# SH2_-_48V_POWER.net
KiCad netlist of a schematic drawn in Altium Designer
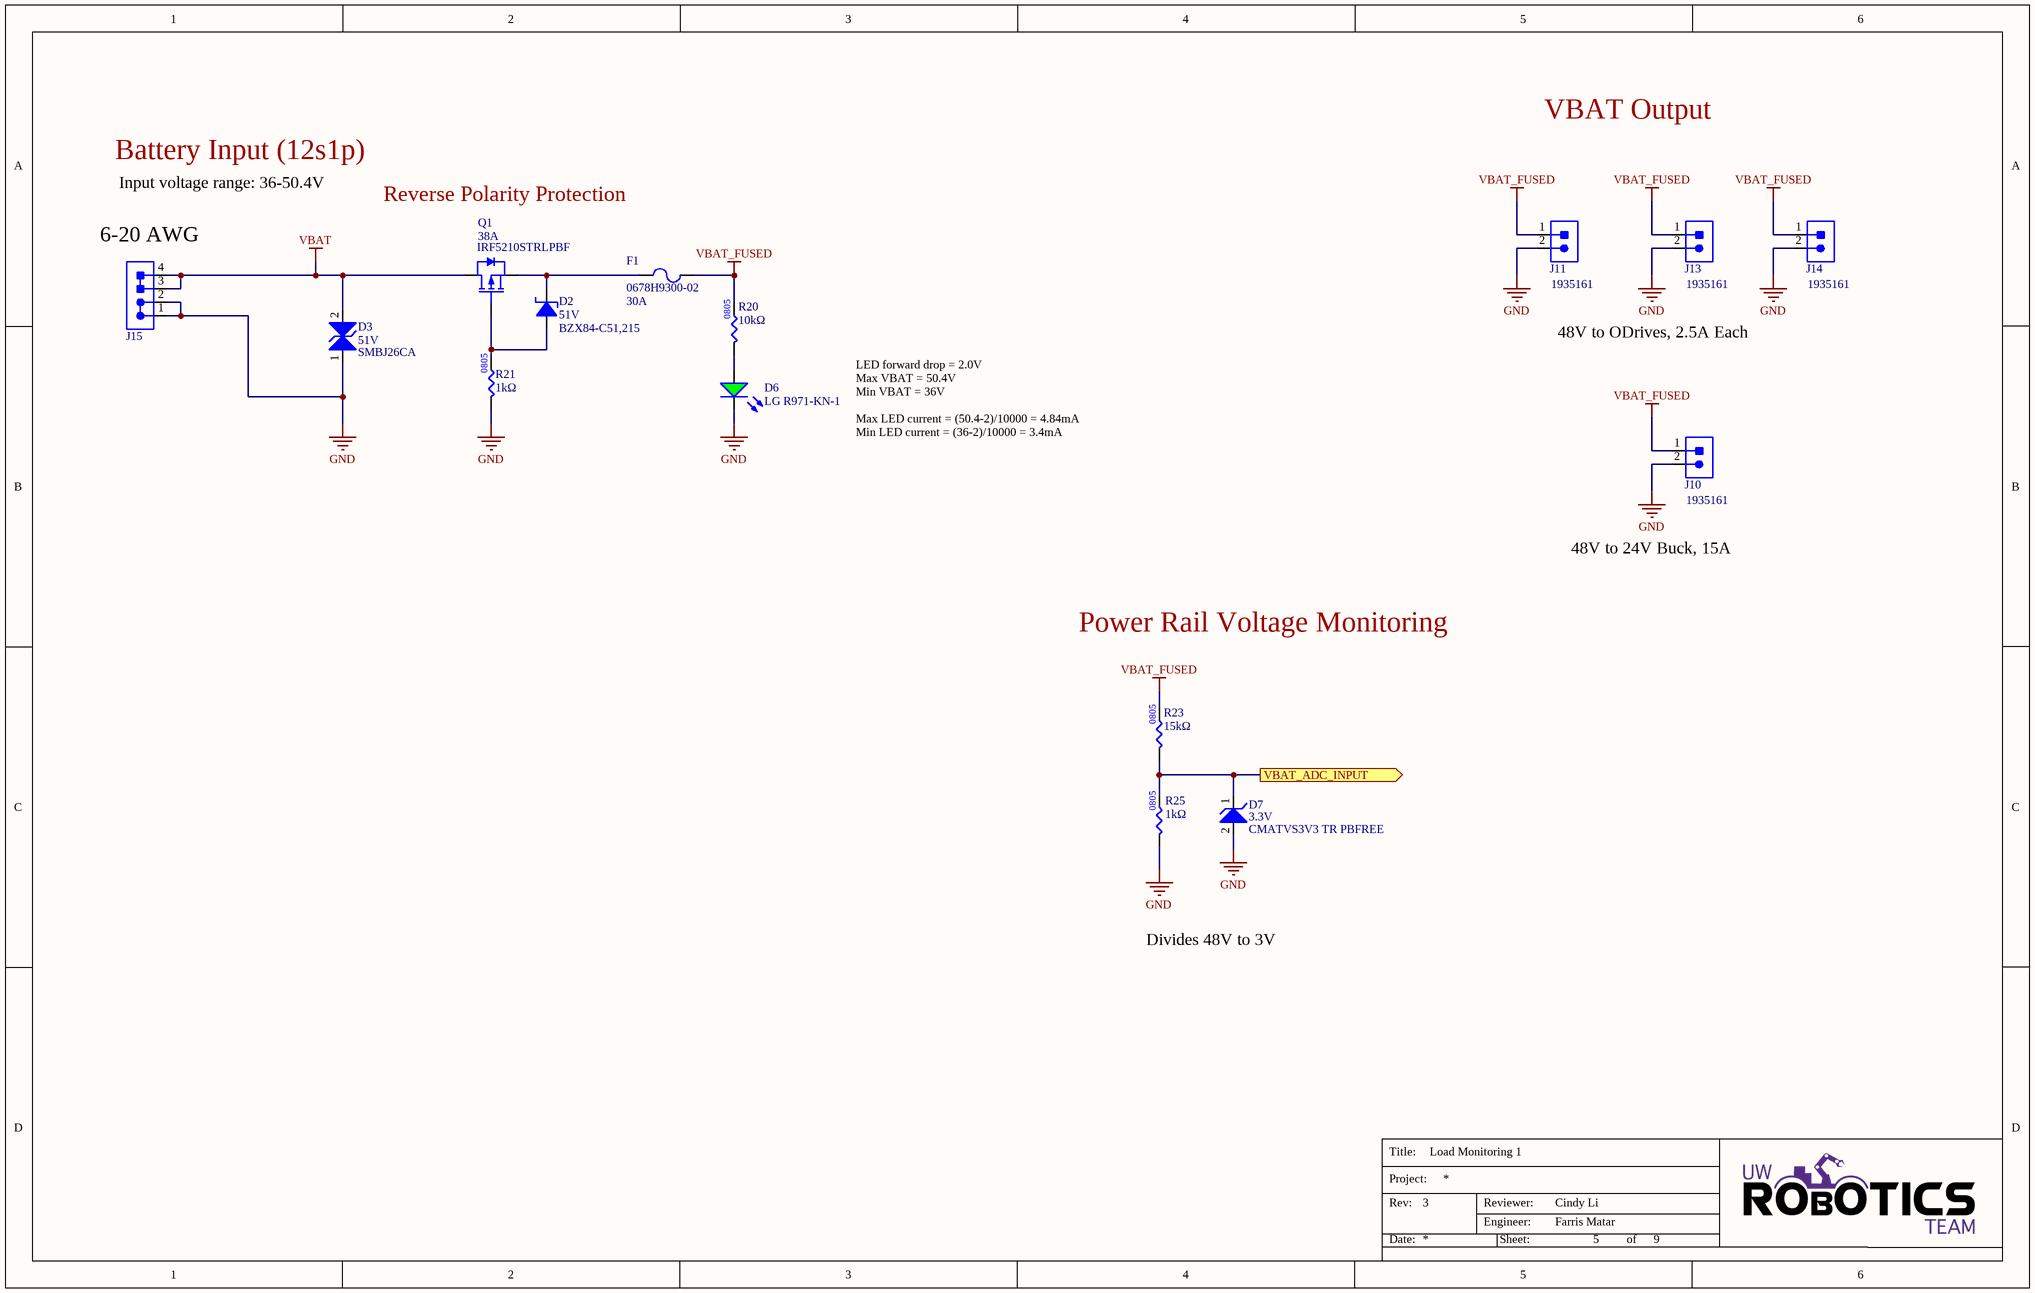
[diagram p0: SH2 - 48V POWER.SchDoc]

(export (version "E")
  (design (tool "Eeschema 10.0.6"))
  (components
    (comp (ref "D2")
      (value "DIO_ZENER_51V")
      (footprint "SOT23-3")
      (description "DIODE ZENER 51V 250MW TO236AB")
      (fields
        (field (name "MANUFACTURER PART NUMBER 1") "BZX84-C51,215")
        (field (name "WORKING VOLTAGE") "51V")
      )
      (libsource (lib "UWRT_Schematic_Library_2020") (part "DIO_ZENER_51V"))
    )
    (comp (ref "D3")
      (value "TVS_DIODE_BIDIR_51V")
      (footprint "TVS_DIODE_BIDIR_SMB")
      (description "TVS DIODE 51VWM 82.4VC DO214AA")
      (fields
        (field (name "MANUFACTURER PART NUMBER 1") "SMBJ26CA")
        (field (name "VOLTAGE - REVERSE STANDOFF (TYP)") "51V")
      )
      (libsource (lib "UWRT_Schematic_Library_2020") (part "TVS_DIODE_BIDIR_51V"))
    )
    (comp (ref "D6")
      (value "LED_GREEN")
      (footprint "LED_0805_GREEN")
      (description "LED GREEN DIFFUSED 0805 SMD")
      (fields (field (name "MANUFACTURER PART NUMBER 1") "LG R971-KN-1"))
      (libsource (lib "UWRT_Schematic_Library_2020") (part "LED_GREEN"))
    )
    (comp (ref "D7")
      (value "TVS_DIODE_UNIDIR_3.3V_7A")
      (footprint "SOD-923")
      (description "TVS DIODE 3.3VWM 11VC SOD923")
      (fields
        (field (name "MANUFACTURER PART NUMBER 1") "CMATVS3V3 TR PBFREE")
        (field (name "VOLTAGE - REVERSE STANDOFF (TYP)") "3.3V")
      )
      (libsource (lib "UWRT_Schematic_Library_2020") (part "TVS_DIODE_UNIDIR_3.3V_7A"))
    )
    (comp (ref "F1")
      (value "FUSE_30A_3912")
      (footprint "FUSE_3912")
      (description "FUSE SMT 3912 ENH BRK 250V 30A")
      (fields
        (field (name "MANUFACTURER PART NUMBER 1") "0678H9300-02")
        (field (name "CURRENT RATING") "30A")
      )
      (libsource (lib "UWRT_Schematic_Library_2020") (part "FUSE_30A_3912"))
    )
    (comp (ref "J10")
      (value "CON_2M_TERM")
      (footprint "1935161")
      (description "TERM BLK 2POS SIDE ENTRY 5MM")
      (fields (field (name "VOLTAGE") "300V") (field (name "MANUFACTURER PART NUMBER 1") "1935161"))
      (libsource (lib "UWRT_Schematic_Library_2020") (part "CON_2M_TERM"))
    )
    (comp (ref "J11")
      (value "CON_2M_TERM")
      (footprint "1935161")
      (description "TERM BLK 2POS SIDE ENTRY 5MM")
      (fields (field (name "VOLTAGE") "300V") (field (name "MANUFACTURER PART NUMBER 1") "1935161"))
      (libsource (lib "UWRT_Schematic_Library_2020") (part "CON_2M_TERM"))
    )
    (comp (ref "J13")
      (value "CON_2M_TERM")
      (footprint "1935161")
      (description "TERM BLK 2POS SIDE ENTRY 5MM")
      (fields (field (name "VOLTAGE") "300V") (field (name "MANUFACTURER PART NUMBER 1") "1935161"))
      (libsource (lib "UWRT_Schematic_Library_2020") (part "CON_2M_TERM"))
    )
    (comp (ref "J14")
      (value "CON_2M_TERM")
      (footprint "1935161")
      (description "TERM BLK 2POS SIDE ENTRY 5MM")
      (fields (field (name "VOLTAGE") "300V") (field (name "MANUFACTURER PART NUMBER 1") "1935161"))
      (libsource (lib "UWRT_Schematic_Library_2020") (part "CON_2M_TERM"))
    )
    (comp (ref "J15")
      (value "CON_2POS_SCREW_TERM")
      (footprint "VP0265540000G")
      (description "TERM BLK 2P SIDE ENT 10.16MM PCB")
      (libsource (lib "UWRT_Schematic_Library_2020") (part "CON_10.16M_2POS_SCREW_TERM"))
    )
    (comp (ref "Q1")
      (value "PMOS_100V_38A")
      (footprint "DPAK254P1524X483-4_3N - new")
      (description "MOSFET P-CH 100V 38A D2PAK")
      (fields
        (field (name "CURRENT - CONTINOUS DRAIN") "38A")
        (field (name "MANUFACTURER PART NUMBER 1") "IRF5210STRLPBF")
      )
      (libsource (lib "UWRT_Schematic_Library_2020") (part "PMOS_100V_38A"))
    )
    (comp (ref "R20")
      (value "10kΩ")
      (footprint "RES0805")
      (description "RES 10K OHM 5% 1/8W 0805")
      (fields (field (name "LCSC PART #") "C17414") (field (name "Comment") "RES_10kΩ_0805_5%"))
      (libsource (lib "UWRT_Schematic_Library_2020") (part "RES_10kΩ_0805_5%"))
    )
    (comp (ref "R21")
      (value "1kΩ")
      (footprint "RES0805")
      (description "RES 1K OHM 1% 1/8W 0805")
      (fields (field (name "LCSC PART #") "C17513") (field (name "Comment") "RES_1kΩ_0805_1%"))
      (libsource (lib "UWRT_Schematic_Library_2020") (part "RES_1kΩ_0805_1%"))
    )
    (comp (ref "R23")
      (value "15kΩ")
      (footprint "RES0805")
      (description "RES 15K OHM 1% 1/8W 0805")
      (fields (field (name "Comment") "RES_15kΩ_0805_1%"))
      (libsource (lib "UWRT_Schematic_Library_2020") (part "RES_15kΩ_0805_1%"))
    )
    (comp (ref "R25")
      (value "1kΩ")
      (footprint "RES0805")
      (description "RES 1K OHM 1% 1/8W 0805")
      (fields (field (name "LCSC PART #") "C17513") (field (name "Comment") "RES_1kΩ_0805_1%_1"))
      (libsource (lib "UWRT_Schematic_Library_2020") (part "RES_1kΩ_0805_1%_1"))
    )
  )
  (nets
    (net (code "1") (name "/VBAT_ADC_INPUT") (class "Default")
      (node (ref "D7") (pin "1") (pinfunction "1_1") (pintype "passive"))
      (node (ref "R23") (pin "1") (pinfunction "1_1") (pintype "passive"))
      (node (ref "R25") (pin "2") (pinfunction "2_2") (pintype "passive"))
    )
    (net (code "2") (name "GND") (class "Default")
      (node (ref "D3") (pin "1") (pinfunction "1_1") (pintype "passive"))
      (node (ref "D6") (pin "2") (pinfunction "K_2") (pintype "passive"))
      (node (ref "D7") (pin "2") (pinfunction "2_2") (pintype "passive"))
      (node (ref "J10") (pin "2") (pinfunction "2_2") (pintype "passive"))
      (node (ref "J11") (pin "2") (pinfunction "2_2") (pintype "passive"))
      (node (ref "J13") (pin "2") (pinfunction "2_2") (pintype "passive"))
      (node (ref "J14") (pin "2") (pinfunction "2_2") (pintype "passive"))
      (node (ref "J15") (pin "1") (pinfunction "1_1") (pintype "passive"))
      (node (ref "J15") (pin "2") (pinfunction "2_2") (pintype "passive"))
      (node (ref "R21") (pin "1") (pinfunction "1_1") (pintype "passive"))
      (node (ref "R25") (pin "1") (pinfunction "1_1") (pintype "passive"))
    )
    (net (code "3") (name "Net-(D2-Anode)") (class "Default")
      (node (ref "D2") (pin "1") (pinfunction "Anode_1") (pintype "passive"))
      (node (ref "Q1") (pin "1") (pinfunction "Gate_1") (pintype "passive"))
      (node (ref "R21") (pin "2") (pinfunction "2_2") (pintype "passive"))
    )
    (net (code "4") (name "Net-(D2-Cathode)") (class "Default")
      (node (ref "D2") (pin "3") (pinfunction "Cathode_3") (pintype "passive"))
      (node (ref "F1") (pin "1") (pinfunction "1_1") (pintype "passive"))
      (node (ref "Q1") (pin "3") (pinfunction "Source_3") (pintype "passive"))
    )
    (net (code "5") (name "Net-(D6-A)") (class "Default")
      (node (ref "D6") (pin "1") (pinfunction "A_1") (pintype "passive"))
      (node (ref "R20") (pin "1") (pinfunction "1_1") (pintype "passive"))
    )
    (net (code "6") (name "VBAT") (class "Default")
      (node (ref "D3") (pin "2") (pinfunction "2_2") (pintype "passive"))
      (node (ref "J15") (pin "3") (pintype "passive"))
      (node (ref "J15") (pin "4") (pintype "passive"))
      (node (ref "Q1") (pin "2") (pinfunction "Drain_2") (pintype "passive"))
    )
    (net (code "7") (name "VBAT_FUSED") (class "Default")
      (node (ref "F1") (pin "2") (pinfunction "2_2") (pintype "passive"))
      (node (ref "J10") (pin "1") (pinfunction "1_1") (pintype "passive"))
      (node (ref "J11") (pin "1") (pinfunction "1_1") (pintype "passive"))
      (node (ref "J13") (pin "1") (pinfunction "1_1") (pintype "passive"))
      (node (ref "J14") (pin "1") (pinfunction "1_1") (pintype "passive"))
      (node (ref "R20") (pin "2") (pinfunction "2_2") (pintype "passive"))
      (node (ref "R23") (pin "2") (pinfunction "2_2") (pintype "passive"))
    )
  )
)
